# Morpheus_IMU.net
KiCad netlist of a schematic drawn in Altium Designer
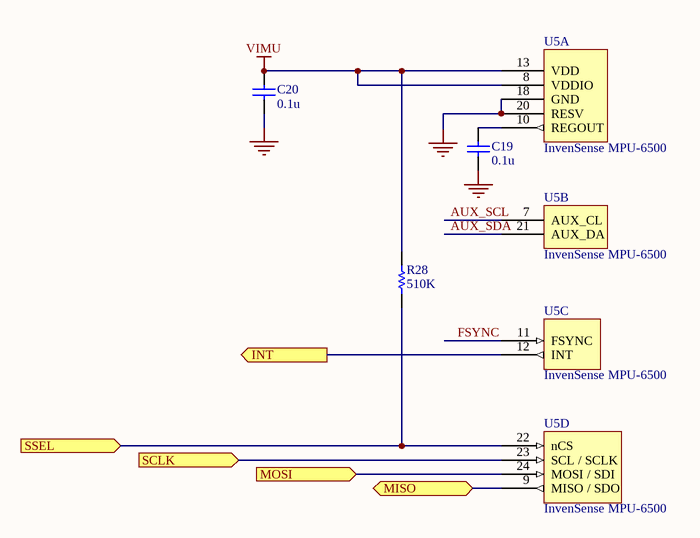
[diagram p0: Morpheus_IMU.SchDoc]

(export (version "E")
  (design (tool "Eeschema 10.0.6"))
  (components
    (comp (ref "C19")
      (value "0.1u")
      (footprint "CAP0402_SENSE_DVT")
      (description "CAP CER 0.1UF 50V 10% X7R 0402")
      (fields (field (name "TOLERANCE") "10%") (field (name "VOLTAGE") "50V"))
      (libsource (lib "Morpheus_pill") (part "C_0.1u_10_50_X7R_0402"))
    )
    (comp (ref "C20")
      (value "0.1u")
      (footprint "CAP0402_SENSE_DVT")
      (description "CAP CER 0.1UF 50V 10% X7R 0402")
      (fields (field (name "TOLERANCE") "10%") (field (name "VOLTAGE") "50V"))
      (libsource (lib "Morpheus_pill") (part "C_0.1u_10_50_X7R_0402"))
    )
    (comp (ref "R28")
      (value "510K")
      (footprint "RES0402_SENSE_DVT")
      (description "RES SMD 510K OHM 5%1/16W 0402")
      (fields (field (name "TOLERANCE") "5 %") (field (name "POWER") "0.1 W"))
      (libsource (lib "Morpheus_pill") (part "R_510K_5_0.1_0402"))
    )
    (comp (ref "U5")
      (value "InvenSense MPU-6500")
      (footprint "QFN-24")
      (description "GYRO/ACCELEROMETER 6AXIS 24QFN")
      (libsource (lib "Morpheus_pill") (part "MPU-6500"))
    )
  )
  (nets
    (net (code "1") (name "/AUX_SCL") (class "Default")
      (node (ref "U5") (pin "7") (pinfunction "AUX_CL_7") (pintype "passive"))
    )
    (net (code "2") (name "/AUX_SDA") (class "Default")
      (node (ref "U5") (pin "21") (pinfunction "AUX_DA_21") (pintype "passive"))
    )
    (net (code "3") (name "/FSYNC") (class "Default")
      (node (ref "U5") (pin "11") (pinfunction "FSYNC_11") (pintype "input"))
    )
    (net (code "4") (name "/INT") (class "Default")
      (node (ref "U5") (pin "12") (pinfunction "INT_12") (pintype "output"))
    )
    (net (code "5") (name "/MISO") (class "Default")
      (node (ref "U5") (pin "9") (pinfunction "MISO_/_SDO_9") (pintype "output"))
    )
    (net (code "6") (name "/MOSI") (class "Default")
      (node (ref "U5") (pin "24") (pinfunction "MOSI_/_SDI_24") (pintype "input"))
    )
    (net (code "7") (name "/SCLK") (class "Default")
      (node (ref "U5") (pin "23") (pinfunction "SCL_/_SCLK_23") (pintype "input"))
    )
    (net (code "8") (name "/SSEL") (class "Default")
      (node (ref "R28") (pin "1") (pinfunction "1_1") (pintype "passive"))
      (node (ref "U5") (pin "22") (pinfunction "nCS_22") (pintype "input"))
    )
    (net (code "9") (name "GND") (class "Default")
      (node (ref "C19") (pin "1") (pinfunction "1_1") (pintype "passive"))
      (node (ref "C20") (pin "1") (pinfunction "1_1") (pintype "passive"))
      (node (ref "U5") (pin "18") (pinfunction "GND_18") (pintype "power_in"))
      (node (ref "U5") (pin "20") (pinfunction "RESV_20") (pintype "passive"))
    )
    (net (code "10") (name "Net-(U5A-REGOUT)") (class "Default")
      (node (ref "C19") (pin "2") (pinfunction "2_2") (pintype "passive"))
      (node (ref "U5") (pin "10") (pinfunction "REGOUT_10") (pintype "output"))
    )
    (net (code "11") (name "VIMU") (class "Default")
      (node (ref "C20") (pin "2") (pinfunction "2_2") (pintype "passive"))
      (node (ref "R28") (pin "2") (pinfunction "2_2") (pintype "passive"))
      (node (ref "U5") (pin "13") (pinfunction "VDD_13") (pintype "power_in"))
      (node (ref "U5") (pin "8") (pinfunction "VDDIO_8") (pintype "power_in"))
    )
  )
)
